# POWER_Management.net
KiCad netlist of a schematic drawn in Altium Designer
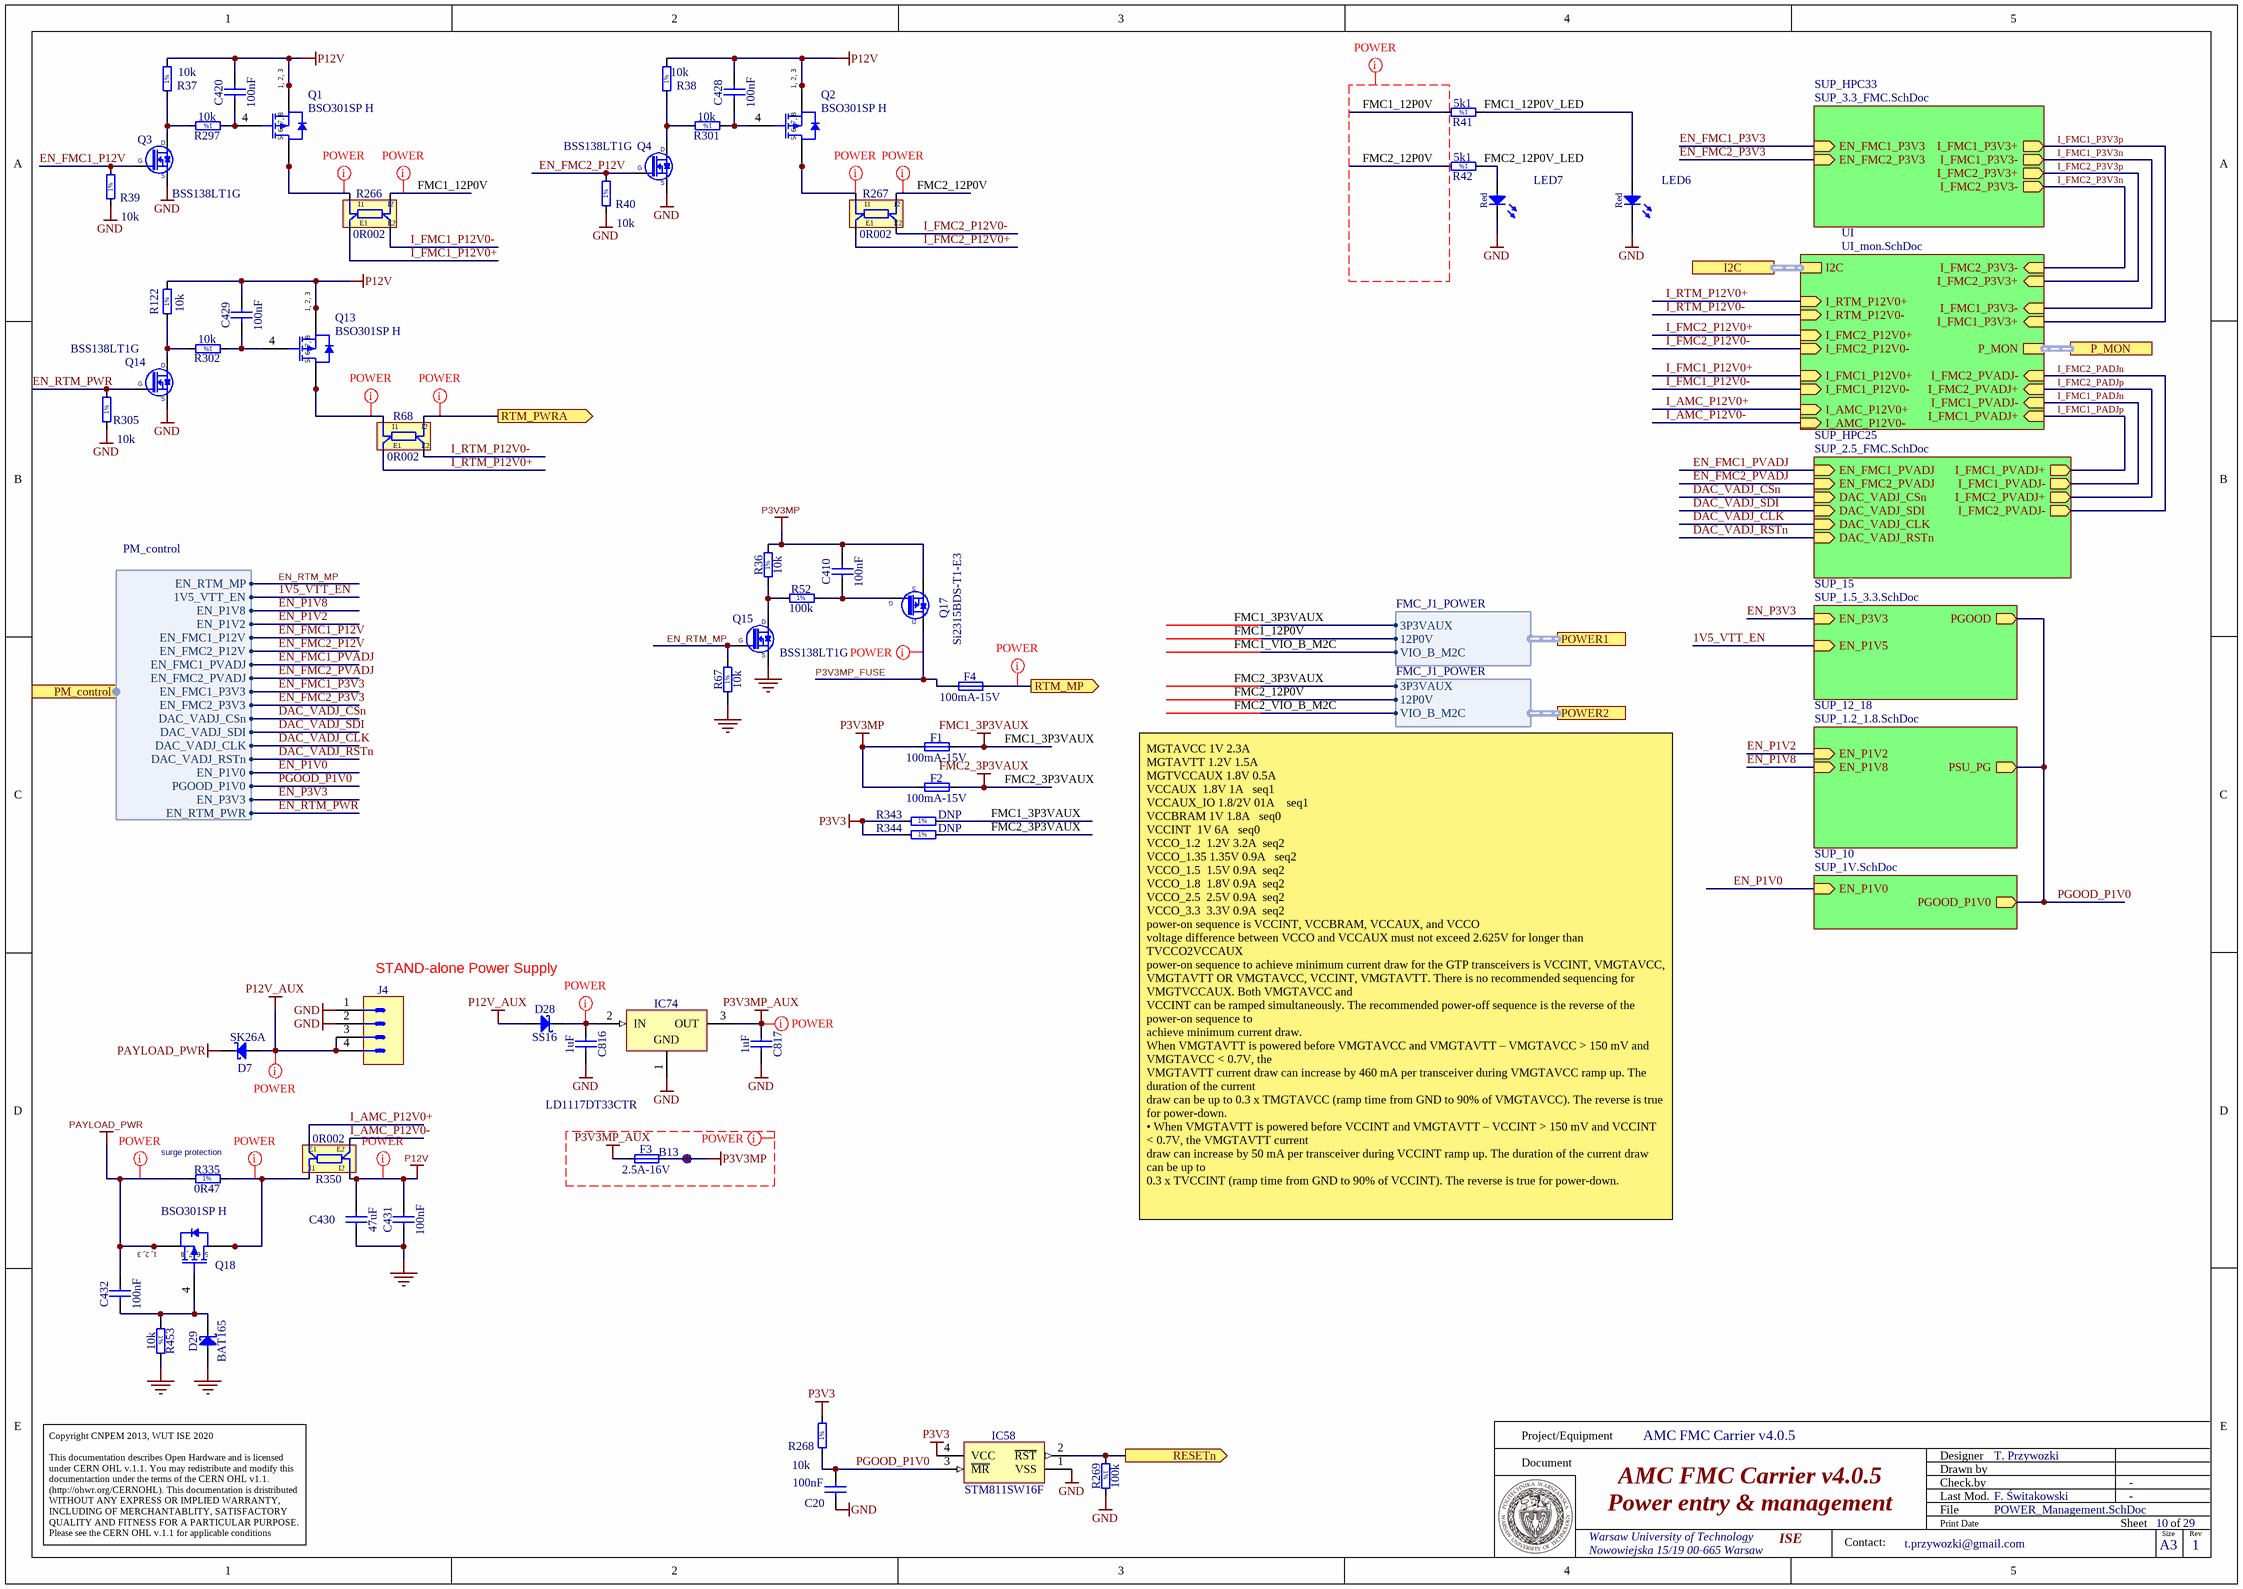
[diagram p0: POWER_Management.SchDoc]

(export (version "E")
  (design (tool "Eeschema 10.0.6"))
  (components
    (comp (ref "B13")
      (value "SMD Pad")
      (footprint "C100")
      (description "Through Hole Pad")
      (fields (field (name "PART NUMBER") "SMD_PAD_D1MM") (field (name "AUTHOR") "CERN DEM JLC"))
      (libsource (lib "Eletro-mechanical") (part "Single SMD Pad (Round)"))
    )
    (comp (ref "C20")
      (value "100nF")
      (footprint "CAPC0603X33N")
      (description "Non-polarised capacitor")
      (fields
        (field (name "PART NUMBER") "CC0201_100NF_6.3V_10%_X5R")
        (field (name "VOLTAGE") "6.3V")
        (field (name "AUTHOR") "CERN DEM JLC")
      )
      (libsource (lib "Capacitors") (part "Capacitor - non polarized"))
    )
    (comp (ref "C410")
      (value "100nF")
      (footprint "CAPC1005X55N")
      (description "Non-polarised capacitor")
      (fields
        (field (name "MANUFACTURER PART NUMBER") "CC0402_100NF_16V_10%_X5R")
        (field (name "MANUFACTURER") "GENERIC")
        (field (name "AUTHOR") "CERN DEM JLC")
      )
      (libsource (lib "Capacitors") (part "Capacitor - non polarized"))
    )
    (comp (ref "C420")
      (value "100nF")
      (footprint "CAPC1005X55N")
      (description "Non-polarised capacitor")
      (fields
        (field (name "MANUFACTURER PART NUMBER") "CC0402_100NF_16V_10%_X5R")
        (field (name "MANUFACTURER") "GENERIC")
        (field (name "AUTHOR") "CERN DEM JLC")
      )
      (libsource (lib "Capacitors") (part "Capacitor - non polarized"))
    )
    (comp (ref "C428")
      (value "100nF")
      (footprint "CAPC1005X55N")
      (description "Non-polarised capacitor")
      (fields
        (field (name "MANUFACTURER PART NUMBER") "CC0402_100NF_16V_10%_X5R")
        (field (name "MANUFACTURER") "GENERIC")
        (field (name "AUTHOR") "CERN DEM JLC")
      )
      (libsource (lib "Capacitors") (part "Capacitor - non polarized"))
    )
    (comp (ref "C429")
      (value "100nF")
      (footprint "CAPC1005X55N")
      (description "Non-polarised capacitor")
      (fields
        (field (name "MANUFACTURER PART NUMBER") "CC0402_100NF_16V_10%_X5R")
        (field (name "MANUFACTURER") "GENERIC")
        (field (name "AUTHOR") "CERN DEM JLC")
      )
      (libsource (lib "Capacitors") (part "Capacitor - non polarized"))
    )
    (comp (ref "C430")
      (value "47uF")
      (footprint "CAPC3216X180N")
      (description "Non-polarised capacitor")
      (fields
        (field (name "MANUFACTURER PART NUMBER") "CC1206_47UF_25V_20%_X5R")
        (field (name "MANUFACTURER") "GENERIC")
        (field (name "AUTHOR") "CERN DEM JLC")
      )
      (libsource (lib "Capacitors") (part "Capacitor - non polarized"))
    )
    (comp (ref "C431")
      (value "100nF")
      (footprint "CAPC1005X55N")
      (description "Non-polarised capacitor")
      (fields
        (field (name "MANUFACTURER PART NUMBER") "CC0402_100NF_16V_10%_X5R")
        (field (name "MANUFACTURER") "GENERIC")
        (field (name "AUTHOR") "CERN DEM JLC")
      )
      (libsource (lib "Capacitors") (part "Capacitor - non polarized"))
    )
    (comp (ref "C432")
      (value "100nF")
      (footprint "CAPC1005X55N")
      (description "Non-polarised capacitor")
      (fields
        (field (name "MANUFACTURER PART NUMBER") "CC0402_100NF_16V_10%_X5R")
        (field (name "MANUFACTURER") "GENERIC")
        (field (name "AUTHOR") "CERN DEM JLC")
      )
      (libsource (lib "Capacitors") (part "Capacitor - non polarized"))
    )
    (comp (ref "C816")
      (value "1uF")
      (footprint "CAPC1608X87N")
      (description "Non-polarised capacitor")
      (fields
        (field (name "PART NUMBER") "CC0603_1UF_16V_10%_X7R")
        (field (name "VOLTAGE") "16V")
        (field (name "AUTHOR") "CERN DEM JLC")
      )
      (libsource (lib "Capacitors") (part "Capacitor - non polarized"))
    )
    (comp (ref "C817")
      (value "1uF")
      (footprint "CAPC1608X87N")
      (description "Non-polarised capacitor")
      (fields
        (field (name "PART NUMBER") "CC0603_1UF_16V_10%_X7R")
        (field (name "VOLTAGE") "16V")
        (field (name "AUTHOR") "CERN DEM JLC")
      )
      (libsource (lib "Capacitors") (part "Capacitor - non polarized"))
    )
    (comp (ref "D7")
      (value "SK26A")
      (footprint "DIOM5126X265N")
      (description "Schottky Diode")
      (fields
        (field (name "VOLTAGE") "60V")
        (field (name "POWER") "2A")
        (field (name "AUTHOR") "CERN DEM JMW")
      )
      (libsource (lib "ICs And Semiconductors") (part "Diode Schottky"))
    )
    (comp (ref "D28")
      (value "SS16")
      (footprint "DIOM5127X229N")
      (description "Schottky Diode")
      (fields
        (field (name "MANUFACTURER") "VISHAY GENERAL SEMICONDUCTOR")
        (field (name "VOLTAGE") "60V")
        (field (name "AUTHOR") "CERN DEM JLC")
      )
      (libsource (lib "ICs And Semiconductors") (part "Diode Schottky"))
    )
    (comp (ref "D29")
      (value "BAT165")
      (footprint "SOD2512X110N")
      (description "Schottky Diode")
      (fields
        (field (name "MANUFACTURER") "INFINEON")
        (field (name "VOLTAGE") "40V")
        (field (name "AUTHOR") "CERN DEM JLC")
      )
      (libsource (lib "ICs And Semiconductors") (part "Diode Schottky"))
    )
    (comp (ref "F1")
      (value "100mA-15V")
      (footprint "FUSR_LITTELFUSE_0805L010")
      (description "Fuse")
      (fields
        (field (name "MANUFACTURER PART NUMBER") "0805L010YR")
        (field (name "MANUFACTURER") "LITTELFUSE")
        (field (name "AUTHOR") "CERN DEM JLC")
      )
      (libsource (lib "Eletro-mechanical") (part "Fuse"))
    )
    (comp (ref "F2")
      (value "100mA-15V")
      (footprint "FUSR_LITTELFUSE_0805L010")
      (description "Fuse")
      (fields
        (field (name "MANUFACTURER PART NUMBER") "0805L010YR")
        (field (name "MANUFACTURER") "LITTELFUSE")
        (field (name "AUTHOR") "CERN DEM JLC")
      )
      (libsource (lib "Eletro-mechanical") (part "Fuse"))
    )
    (comp (ref "F3")
      (value "2.5A-16V")
      (footprint "FUSR_BOURNS_MF-MSMF_STYLE2")
      (description "Fuse")
      (fields
        (field (name "PART NUMBER") "FUSR_BOURNS_MF-MSMF250/16X-2")
        (field (name "MANUFACTURER") "BOURNS")
        (field (name "AUTHOR") "CERN DEM JLC")
      )
      (libsource (lib "Eletro-mechanical") (part "Fuse"))
    )
    (comp (ref "F4")
      (value "100mA-15V")
      (footprint "FUSR_LITTELFUSE_0805L010")
      (description "Fuse")
      (fields
        (field (name "MANUFACTURER PART NUMBER") "0805L010YR")
        (field (name "MANUFACTURER") "LITTELFUSE")
        (field (name "AUTHOR") "CERN DEM JLC")
      )
      (libsource (lib "Eletro-mechanical") (part "Fuse"))
    )
    (comp (ref "IC58")
      (value "STM811SW16F")
      (footprint "SOT143N")
      (description "Microprocessor Reset Circuit")
      (fields (field (name "MANUFACTURER") "ST MICROELECTRONICS") (field (name "AUTHOR") "CERN DEM JLC"))
      (libsource (lib "ICs And Semiconductors") (part "STM811"))
    )
    (comp (ref "IC74")
      (value "LD1117DT33CTR")
      (footprint "TO228P972X240-3N-R540X510")
      (description "3-Terminal Regulator 1=GND 2=IN 3=OUT")
      (fields (field (name "MANUFACTURER") "ST MICROELECTRONICS") (field (name "AUTHOR") "CERN DEM JLC"))
      (libsource (lib "ICs And Semiconductors") (part "REG3 1GND-2IN-3OUT"))
    )
    (comp (ref "J4")
      (value "Mini-Fit Jr.™")
      (footprint "MOLEX_39-28-1043")
      (description "Connector 4 Male")
      (fields
        (field (name "PART NUMBER") "MOLEX_39-28-1043")
        (field (name "MANUFACTURER") "MOLEX")
        (field (name "AUTHOR") "CERN DEM JLC")
      )
      (libsource (lib "Connectors") (part "Connector 4 Male"))
    )
    (comp (ref "LED6")
      (value "Red")
      (footprint "LED_KINGBRIGHT_KPH-1608SURCK")
      (description "LED Red 1C 2A")
      (fields
        (field (name "PART NUMBER") "LED_KINGBRIGHT_KPH-1608SURCK")
        (field (name "MANUFACTURER") "KINGBRIGHT")
        (field (name "AUTHOR") "CERN DEM JLC")
      )
      (libsource (lib "ICs And Semiconductors") (part "LED Red 1C 2A"))
    )
    (comp (ref "LED7")
      (value "Red")
      (footprint "LED_KINGBRIGHT_KPH-1608SURCK")
      (description "LED Red 1C 2A")
      (fields
        (field (name "PART NUMBER") "LED_KINGBRIGHT_KPH-1608SURCK")
        (field (name "MANUFACTURER") "KINGBRIGHT")
        (field (name "AUTHOR") "CERN DEM JLC")
      )
      (libsource (lib "ICs And Semiconductors") (part "LED Red 1C 2A"))
    )
    (comp (ref "Q1")
      (value "BSO301SP H")
      (footprint "INF-P-DSO-8-3_L")
      (fields (field (name "MANUFACTURER") "Infineon"))
      (libsource (lib "Altium Content Vault") (part "INF-PEMOS-SSSGDDDD-8"))
    )
    (comp (ref "Q2")
      (value "BSO301SP H")
      (footprint "INF-P-DSO-8-3_L")
      (fields (field (name "MANUFACTURER") "Infineon"))
      (libsource (lib "Altium Content Vault") (part "INF-PEMOS-SSSGDDDD-8"))
    )
    (comp (ref "Q3")
      (value "BSS138LT1G")
      (footprint "SOT95P240X110-3N")
      (description "N-CHANNEL MOSFET WITH DIODE")
      (fields (field (name "MANUFACTURER") "ON SEMICONDUCTOR") (field (name "AUTHOR") "CERN DEM JLC"))
      (libsource (lib "ICs And Semiconductors") (part "N-MOSFET-D 1G 2S 3D"))
    )
    (comp (ref "Q4")
      (value "BSS138LT1G")
      (footprint "SOT95P240X110-3N")
      (description "N-CHANNEL MOSFET WITH DIODE")
      (fields (field (name "MANUFACTURER") "ON SEMICONDUCTOR") (field (name "AUTHOR") "CERN DEM JLC"))
      (libsource (lib "ICs And Semiconductors") (part "N-MOSFET-D 1G 2S 3D"))
    )
    (comp (ref "Q13")
      (value "BSO301SP H")
      (footprint "INF-P-DSO-8-3_L")
      (fields (field (name "MANUFACTURER") "Infineon"))
      (libsource (lib "Altium Content Vault") (part "INF-PEMOS-SSSGDDDD-8"))
    )
    (comp (ref "Q14")
      (value "BSS138LT1G")
      (footprint "SOT95P240X110-3N")
      (description "N-CHANNEL MOSFET WITH DIODE")
      (fields (field (name "MANUFACTURER") "ON SEMICONDUCTOR") (field (name "AUTHOR") "CERN DEM JLC"))
      (libsource (lib "ICs And Semiconductors") (part "N-MOSFET-D 1G 2S 3D"))
    )
    (comp (ref "Q15")
      (value "BSS138LT1G")
      (footprint "SOT95P240X110-3N")
      (description "N-CHANNEL MOSFET WITH DIODE")
      (fields (field (name "MANUFACTURER") "ON SEMICONDUCTOR") (field (name "AUTHOR") "CERN DEM JLC"))
      (libsource (lib "ICs And Semiconductors") (part "N-MOSFET-D 1G 2S 3D"))
    )
    (comp (ref "Q17")
      (value "Si2315BDS-T1-E3")
      (footprint "SOT95P237X112-3N")
      (description "P-CHANNEL MOSFET WITH DIODE")
      (fields (field (name "MANUFACTURER") "VISHAY SILICONIX") (field (name "AUTHOR") "CERN DEM JLC"))
      (libsource (lib "ICs And Semiconductors") (part "P-MOSFET-D 1G 2S 3D"))
    )
    (comp (ref "Q18")
      (value "BSO301SP H")
      (footprint "INF-P-DSO-8-3_L")
      (fields (field (name "MANUFACTURER") "Infineon"))
      (libsource (lib "Altium Content Vault") (part "INF-PEMOS-SSSGDDDD-8"))
    )
    (comp (ref "R36")
      (value "10k")
      (footprint "RESC1005X40N")
      (description "Resistor - 1%")
      (fields
        (field (name "MANUFACTURER PART NUMBER") "R0402_10K_1%_0.0625W_100PPM")
        (field (name "MANUFACTURER") "GENERIC")
        (field (name "AUTHOR") "CERN DEM JLC")
      )
      (libsource (lib "Resistors") (part "Resistor - 1%"))
    )
    (comp (ref "R37")
      (value "10k")
      (footprint "RESC1005X40N")
      (description "Resistor - 1%")
      (fields
        (field (name "PART NUMBER") "R0402_10K_1%_0.0625W_100PPM")
        (field (name "POWER") "0.0625W")
        (field (name "AUTHOR") "CERN DEM JLC")
      )
      (libsource (lib "Resistors") (part "Resistor - 1%"))
    )
    (comp (ref "R38")
      (value "10k")
      (footprint "RESC1005X40N")
      (description "Resistor - 1%")
      (fields
        (field (name "PART NUMBER") "R0402_10K_1%_0.0625W_100PPM")
        (field (name "POWER") "0.0625W")
        (field (name "AUTHOR") "CERN DEM JLC")
      )
      (libsource (lib "Resistors") (part "Resistor - 1%"))
    )
    (comp (ref "R39")
      (value "10k")
      (footprint "RESC1005X40N")
      (description "Resistor - 1%")
      (fields
        (field (name "PART NUMBER") "R0402_10K_1%_0.0625W_100PPM")
        (field (name "POWER") "0.0625W")
        (field (name "AUTHOR") "CERN DEM JLC")
      )
      (libsource (lib "Resistors") (part "Resistor - 1%"))
    )
    (comp (ref "R40")
      (value "10k")
      (footprint "RESC1005X40N")
      (description "Resistor - 1%")
      (fields
        (field (name "PART NUMBER") "R0402_10K_1%_0.0625W_100PPM")
        (field (name "POWER") "0.0625W")
        (field (name "AUTHOR") "CERN DEM JLC")
      )
      (libsource (lib "Resistors") (part "Resistor - 1%"))
    )
    (comp (ref "R41")
      (value "5k1")
      (footprint "RESC1608X55N")
      (description "Resistor - 1%")
      (fields
        (field (name "PART NUMBER") "R0603_5K1_1%_0.1W_100PPM")
        (field (name "POWER") "0.1W")
        (field (name "AUTHOR") "CERN DEM JLC")
      )
      (libsource (lib "Resistors") (part "Resistor - 1%"))
    )
    (comp (ref "R42")
      (value "5k1")
      (footprint "RESC1608X55N")
      (description "Resistor - 1%")
      (fields
        (field (name "PART NUMBER") "R0603_5K1_1%_0.1W_100PPM")
        (field (name "POWER") "0.1W")
        (field (name "AUTHOR") "CERN DEM JLC")
      )
      (libsource (lib "Resistors") (part "Resistor - 1%"))
    )
    (comp (ref "R52")
      (value "100k")
      (footprint "RESC1005X40N")
      (description "Resistor - 1%")
      (fields
        (field (name "MANUFACTURER PART NUMBER") "R0402_100K_1%_0.0625W_100PPM")
        (field (name "MANUFACTURER") "GENERIC")
        (field (name "AUTHOR") "CERN DEM JLC")
      )
      (libsource (lib "Resistors") (part "Resistor - 1%"))
    )
    (comp (ref "R67")
      (value "10k")
      (footprint "RESC1005X40N")
      (description "Resistor - 1%")
      (fields
        (field (name "MANUFACTURER PART NUMBER") "R0402_10K_1%_0.0625W_100PPM")
        (field (name "MANUFACTURER") "GENERIC")
        (field (name "AUTHOR") "CERN DEM JLC")
      )
      (libsource (lib "Resistors") (part "Resistor - 1%"))
    )
    (comp (ref "R68")
      (value "0R002")
      (footprint "RES_VISHAY_WSK2512_0R005-0R2")
      (description "Power and Current Sensing Resistor")
      (fields
        (field (name "PART NUMBER") "R2512_0R002_1%_1W_35PPM_VISHAY_WSK")
        (field (name "POWER") "1W")
        (field (name "AUTHOR") "CERN DEM MR")
      )
      (libsource (lib "Resistors") (part "Current Sense Resistor"))
    )
    (comp (ref "R122")
      (value "10k")
      (footprint "RESC1005X40N")
      (description "Resistor - 1%")
      (fields
        (field (name "PART NUMBER") "R0402_10K_1%_0.0625W_100PPM")
        (field (name "POWER") "0.0625W")
        (field (name "AUTHOR") "CERN DEM JLC")
      )
      (libsource (lib "Resistors") (part "Resistor - 1%"))
    )
    (comp (ref "R266")
      (value "0R002")
      (footprint "RES_VISHAY_WSK2512_0R005-0R2")
      (description "Power and Current Sensing Resistor")
      (fields
        (field (name "PART NUMBER") "R2512_0R002_1%_1W_35PPM_VISHAY_WSK")
        (field (name "POWER") "1W")
        (field (name "AUTHOR") "CERN DEM MR")
      )
      (libsource (lib "Resistors") (part "Current Sense Resistor"))
    )
    (comp (ref "R267")
      (value "0R002")
      (footprint "RES_VISHAY_WSK2512_0R005-0R2")
      (description "Power and Current Sensing Resistor")
      (fields
        (field (name "PART NUMBER") "R2512_0R002_1%_1W_35PPM_VISHAY_WSK")
        (field (name "POWER") "1W")
        (field (name "AUTHOR") "CERN DEM MR")
      )
      (libsource (lib "Resistors") (part "Current Sense Resistor"))
    )
    (comp (ref "R268")
      (value "10k")
      (footprint "RESC1005X40N")
      (description "Resistor - 1%")
      (fields
        (field (name "PART NUMBER") "R0402_10K_1%_0.0625W_100PPM")
        (field (name "POWER") "0.0625W")
        (field (name "AUTHOR") "CERN DEM JLC")
      )
      (libsource (lib "Resistors") (part "Resistor - 1%"))
    )
    (comp (ref "R269")
      (value "100k")
      (footprint "RESC1005X40N")
      (description "Resistor - 1%")
      (fields
        (field (name "PART NUMBER") "R0402_100K_1%_0.0625W_100PPM")
        (field (name "POWER") "0.0625W")
        (field (name "AUTHOR") "CERN DEM JLC")
      )
      (libsource (lib "Resistors") (part "Resistor - 1%"))
    )
    (comp (ref "R297")
      (value "10k")
      (footprint "RESC1005X40N")
      (description "Resistor - 1%")
      (fields
        (field (name "MANUFACTURER PART NUMBER") "R0402_10K_1%_0.0625W_100PPM")
        (field (name "MANUFACTURER") "GENERIC")
        (field (name "AUTHOR") "CERN DEM JLC")
      )
      (libsource (lib "Resistors") (part "Resistor - 1%"))
    )
    (comp (ref "R301")
      (value "10k")
      (footprint "RESC1005X40N")
      (description "Resistor - 1%")
      (fields
        (field (name "MANUFACTURER PART NUMBER") "R0402_10K_1%_0.0625W_100PPM")
        (field (name "MANUFACTURER") "GENERIC")
        (field (name "AUTHOR") "CERN DEM JLC")
      )
      (libsource (lib "Resistors") (part "Resistor - 1%"))
    )
    (comp (ref "R302")
      (value "10k")
      (footprint "RESC1005X40N")
      (description "Resistor - 1%")
      (fields
        (field (name "MANUFACTURER PART NUMBER") "R0402_10K_1%_0.0625W_100PPM")
        (field (name "MANUFACTURER") "GENERIC")
        (field (name "AUTHOR") "CERN DEM JLC")
      )
      (libsource (lib "Resistors") (part "Resistor - 1%"))
    )
    (comp (ref "R305")
      (value "10k")
      (footprint "RESC1005X40N")
      (description "Resistor - 1%")
      (fields
        (field (name "PART NUMBER") "R0402_10K_1%_0.0625W_100PPM")
        (field (name "POWER") "0.0625W")
        (field (name "AUTHOR") "CERN DEM JLC")
      )
      (libsource (lib "Resistors") (part "Resistor - 1%"))
    )
    (comp (ref "R335")
      (value "0R47")
      (footprint "RESC3216X65N")
      (description "Resistor - 1%")
      (fields
        (field (name "MANUFACTURER PART NUMBER") "RL1206FR-7W0R47  (35051914707)")
        (field (name "MANUFACTURER") "YAGEO PHYCOMP")
        (field (name "AUTHOR") "CERN DEM JLC")
      )
      (libsource (lib "Resistors") (part "Resistor - 1%"))
    )
    (comp (ref "R343")
      (value "DNP")
      (footprint "RESC1005X40N")
      (description "Resistor - 1%")
      (fields
        (field (name "PART NUMBER") "R0402_0R_JUMPER")
        (field (name "MANUFACTURER") "GENERIC")
        (field (name "AUTHOR") "CERN DEM JLC")
      )
      (libsource (lib "Resistors") (part "Resistor - 1%"))
    )
    (comp (ref "R344")
      (value "DNP")
      (footprint "RESC1005X40N")
      (description "Resistor - 1%")
      (fields
        (field (name "PART NUMBER") "R0402_0R_JUMPER")
        (field (name "MANUFACTURER") "GENERIC")
        (field (name "AUTHOR") "CERN DEM JLC")
      )
      (libsource (lib "Resistors") (part "Resistor - 1%"))
    )
    (comp (ref "R350")
      (value "0R002")
      (footprint "RES_VISHAY_WSK2512_0R005-0R2")
      (description "Power and Current Sensing Resistor")
      (fields
        (field (name "PART NUMBER") "R2512_0R002_1%_1W_35PPM_VISHAY_WSK")
        (field (name "POWER") "1W")
        (field (name "AUTHOR") "CERN DEM MR")
      )
      (libsource (lib "") (part "Current Sense Resistor_1"))
    )
    (comp (ref "R453")
      (value "10k")
      (footprint "RESC1005X40N")
      (description "Resistor - 1%")
      (fields
        (field (name "MANUFACTURER PART NUMBER") "R0402_10K_1%_0.0625W_100PPM")
        (field (name "MANUFACTURER") "GENERIC")
        (field (name "AUTHOR") "CERN DEM JLC")
      )
      (libsource (lib "Resistors") (part "Resistor - 1%"))
    )
  )
  (nets
    (net (code "11") (name "/EN_FMC1_P12V") (class "Default")
      (node (ref "Q3") (pin "1") (pinfunction "G_1") (pintype "passive"))
      (node (ref "R39") (pin "2") (pinfunction "2_2") (pintype "passive"))
    )
    (net (code "14") (name "/EN_FMC2_P12V") (class "Default")
      (node (ref "Q4") (pin "1") (pinfunction "G_1") (pintype "passive"))
      (node (ref "R40") (pin "2") (pinfunction "2_2") (pintype "passive"))
    )
    (net (code "20") (name "/EN_RTM_MP") (class "Default")
      (node (ref "Q15") (pin "1") (pinfunction "G_1") (pintype "passive"))
      (node (ref "R67") (pin "2") (pinfunction "2_2") (pintype "passive"))
    )
    (net (code "21") (name "/EN_RTM_PWR") (class "Default")
      (node (ref "Q14") (pin "1") (pinfunction "G_1") (pintype "passive"))
      (node (ref "R305") (pin "2") (pinfunction "2_2") (pintype "passive"))
    )
    (net (code "22") (name "/FMC1_12P0V") (class "Default")
      (node (ref "R266") (pin "I2") (pinfunction "I2_I2") (pintype "passive"))
      (node (ref "R41") (pin "2") (pinfunction "2_2") (pintype "passive"))
    )
    (net (code "23") (name "/FMC1_12P0V_LED") (class "Default")
      (node (ref "LED6") (pin "2") (pinfunction "A_2") (pintype "passive"))
      (node (ref "R41") (pin "1") (pinfunction "1_1") (pintype "passive"))
    )
    (net (code "25") (name "/FMC2_12P0V") (class "Default")
      (node (ref "R267") (pin "I2") (pinfunction "I2_I2") (pintype "passive"))
      (node (ref "R42") (pin "2") (pinfunction "2_2") (pintype "passive"))
    )
    (net (code "26") (name "/FMC2_12P0V_LED") (class "Default")
      (node (ref "LED7") (pin "2") (pinfunction "A_2") (pintype "passive"))
      (node (ref "R42") (pin "1") (pinfunction "1_1") (pintype "passive"))
    )
    (net (code "29") (name "/I_AMC_P12V0+") (class "Default")
      (node (ref "R350") (pin "E1") (pinfunction "E1_E1") (pintype "passive"))
    )
    (net (code "30") (name "/I_AMC_P12V0-") (class "Default")
      (node (ref "R350") (pin "E2") (pinfunction "E2_E2") (pintype "passive"))
    )
    (net (code "33") (name "/I_FMC1_P12V0+") (class "Default")
      (node (ref "R266") (pin "E1") (pinfunction "E1_E1") (pintype "passive"))
    )
    (net (code "34") (name "/I_FMC1_P12V0-") (class "Default")
      (node (ref "R266") (pin "E2") (pinfunction "E2_E2") (pintype "passive"))
    )
    (net (code "39") (name "/I_FMC2_P12V0+") (class "Default")
      (node (ref "R267") (pin "E1") (pinfunction "E1_E1") (pintype "passive"))
    )
    (net (code "40") (name "/I_FMC2_P12V0-") (class "Default")
      (node (ref "R267") (pin "E2") (pinfunction "E2_E2") (pintype "passive"))
    )
    (net (code "43") (name "/I_RTM_P12V0+") (class "Default")
      (node (ref "R68") (pin "E1") (pinfunction "E1_E1") (pintype "passive"))
    )
    (net (code "44") (name "/I_RTM_P12V0-") (class "Default")
      (node (ref "R68") (pin "E2") (pinfunction "E2_E2") (pintype "passive"))
    )
    (net (code "45") (name "/P3V3MP_FUSE") (class "Default")
      (node (ref "F4") (pin "1") (pinfunction "1_1") (pintype "passive"))
      (node (ref "Q17") (pin "3") (pinfunction "D_3") (pintype "passive"))
    )
    (net (code "46") (name "/PGOOD_P1V0") (class "Default")
      (node (ref "C20") (pin "1") (pinfunction "1_1") (pintype "passive"))
      (node (ref "IC58") (pin "3") (pinfunction "~{MR}_3") (pintype "input"))
      (node (ref "R268") (pin "1") (pinfunction "1_1") (pintype "passive"))
    )
    (net (code "48") (name "/RESETn") (class "Default")
      (node (ref "IC58") (pin "2") (pinfunction "~{RST}_2") (pintype "output"))
      (node (ref "R269") (pin "1") (pinfunction "1_1") (pintype "passive"))
    )
    (net (code "49") (name "/RTM_MP") (class "Default")
      (node (ref "F4") (pin "2") (pinfunction "2_2") (pintype "passive"))
    )
    (net (code "50") (name "/RTM_PWRA") (class "Default")
      (node (ref "R68") (pin "I2") (pinfunction "I2_I2") (pintype "passive"))
    )
    (net (code "53") (name "FMC1_3P3VAUX") (class "Default")
      (node (ref "F1") (pin "2") (pinfunction "2_2") (pintype "passive"))
      (node (ref "R343") (pin "2") (pinfunction "2_2") (pintype "passive"))
    )
    (net (code "54") (name "FMC2_3P3VAUX") (class "Default")
      (node (ref "F2") (pin "2") (pinfunction "2_2") (pintype "passive"))
      (node (ref "R344") (pin "2") (pinfunction "2_2") (pintype "passive"))
    )
    (net (code "55") (name "GND") (class "Default")
      (node (ref "C20") (pin "2") (pinfunction "2_2") (pintype "passive"))
      (node (ref "C430") (pin "1") (pinfunction "1_1") (pintype "passive"))
      (node (ref "C431") (pin "1") (pinfunction "1_1") (pintype "passive"))
      (node (ref "C816") (pin "2") (pinfunction "2_2") (pintype "passive"))
      (node (ref "C817") (pin "2") (pinfunction "2_2") (pintype "passive"))
      (node (ref "D29") (pin "2") (pinfunction "A_2") (pintype "passive"))
      (node (ref "IC58") (pin "1") (pinfunction "VSS_1") (pintype "power_in"))
      (node (ref "IC74") (pin "1") (pinfunction "GND_1") (pintype "power_in"))
      (node (ref "J4") (pin "1") (pinfunction "1_1") (pintype "passive"))
      (node (ref "J4") (pin "2") (pinfunction "2_2") (pintype "passive"))
      (node (ref "LED6") (pin "1") (pinfunction "C_1") (pintype "passive"))
      (node (ref "LED7") (pin "1") (pinfunction "C_1") (pintype "passive"))
      (node (ref "Q14") (pin "2") (pinfunction "S_2") (pintype "passive"))
      (node (ref "Q15") (pin "2") (pinfunction "S_2") (pintype "passive"))
      (node (ref "Q3") (pin "2") (pinfunction "S_2") (pintype "passive"))
      (node (ref "Q4") (pin "2") (pinfunction "S_2") (pintype "passive"))
      (node (ref "R269") (pin "2") (pinfunction "2_2") (pintype "passive"))
      (node (ref "R305") (pin "1") (pinfunction "1_1") (pintype "passive"))
      (node (ref "R39") (pin "1") (pinfunction "1_1") (pintype "passive"))
      (node (ref "R40") (pin "1") (pinfunction "1_1") (pintype "passive"))
      (node (ref "R453") (pin "2") (pinfunction "2_2") (pintype "passive"))
      (node (ref "R67") (pin "1") (pinfunction "1_1") (pintype "passive"))
    )
    (net (code "56") (name "Net-(D28-C)") (class "Default")
      (node (ref "C816") (pin "1") (pinfunction "1_1") (pintype "passive"))
      (node (ref "D28") (pin "1") (pinfunction "C_1") (pintype "passive"))
      (node (ref "IC74") (pin "2") (pinfunction "IN_2") (pintype "input"))
    )
    (net (code "57") (name "Net-(D29-C)") (class "Default")
      (node (ref "C432") (pin "1") (pinfunction "1_1") (pintype "passive"))
      (node (ref "D29") (pin "1") (pinfunction "C_1") (pintype "passive"))
      (node (ref "Q18") (pin "4") (pinfunction "GATE_4") (pintype "passive"))
      (node (ref "R453") (pin "1") (pinfunction "1_1") (pintype "passive"))
    )
    (net (code "58") (name "Net-(Q1-DRAIN-Pad5)") (class "Default")
      (node (ref "Q1") (pin "5") (pinfunction "DRAIN_5") (pintype "passive"))
      (node (ref "Q1") (pin "6") (pinfunction "DRAIN_6") (pintype "passive"))
      (node (ref "Q1") (pin "7") (pinfunction "DRAIN_7") (pintype "passive"))
      (node (ref "Q1") (pin "8") (pinfunction "DRAIN_8") (pintype "passive"))
      (node (ref "R266") (pin "I1") (pinfunction "I1_I1") (pintype "passive"))
    )
    (net (code "59") (name "Net-(Q1-GATE)") (class "Default")
      (node (ref "C420") (pin "1") (pinfunction "1_1") (pintype "passive"))
      (node (ref "Q1") (pin "4") (pinfunction "GATE_4") (pintype "passive"))
      (node (ref "R297") (pin "1") (pinfunction "1_1") (pintype "passive"))
    )
    (net (code "60") (name "Net-(Q2-DRAIN-Pad5)") (class "Default")
      (node (ref "Q2") (pin "5") (pinfunction "DRAIN_5") (pintype "passive"))
      (node (ref "Q2") (pin "6") (pinfunction "DRAIN_6") (pintype "passive"))
      (node (ref "Q2") (pin "7") (pinfunction "DRAIN_7") (pintype "passive"))
      (node (ref "Q2") (pin "8") (pinfunction "DRAIN_8") (pintype "passive"))
      (node (ref "R267") (pin "I1") (pinfunction "I1_I1") (pintype "passive"))
    )
    (net (code "61") (name "Net-(Q2-GATE)") (class "Default")
      (node (ref "C428") (pin "1") (pinfunction "1_1") (pintype "passive"))
      (node (ref "Q2") (pin "4") (pinfunction "GATE_4") (pintype "passive"))
      (node (ref "R301") (pin "1") (pinfunction "1_1") (pintype "passive"))
    )
    (net (code "62") (name "Net-(Q3-D)") (class "Default")
      (node (ref "Q3") (pin "3") (pinfunction "D_3") (pintype "passive"))
      (node (ref "R297") (pin "2") (pinfunction "2_2") (pintype "passive"))
      (node (ref "R37") (pin "1") (pinfunction "1_1") (pintype "passive"))
    )
    (net (code "63") (name "Net-(Q4-D)") (class "Default")
      (node (ref "Q4") (pin "3") (pinfunction "D_3") (pintype "passive"))
      (node (ref "R301") (pin "2") (pinfunction "2_2") (pintype "passive"))
      (node (ref "R38") (pin "1") (pinfunction "1_1") (pintype "passive"))
    )
    (net (code "64") (name "Net-(Q13-DRAIN-Pad5)") (class "Default")
      (node (ref "Q13") (pin "5") (pinfunction "DRAIN_5") (pintype "passive"))
      (node (ref "Q13") (pin "6") (pinfunction "DRAIN_6") (pintype "passive"))
      (node (ref "Q13") (pin "7") (pinfunction "DRAIN_7") (pintype "passive"))
      (node (ref "Q13") (pin "8") (pinfunction "DRAIN_8") (pintype "passive"))
      (node (ref "R68") (pin "I1") (pinfunction "I1_I1") (pintype "passive"))
    )
    (net (code "65") (name "Net-(Q13-GATE)") (class "Default")
      (node (ref "C429") (pin "1") (pinfunction "1_1") (pintype "passive"))
      (node (ref "Q13") (pin "4") (pinfunction "GATE_4") (pintype "passive"))
      (node (ref "R302") (pin "1") (pinfunction "1_1") (pintype "passive"))
    )
    (net (code "66") (name "Net-(Q14-D)") (class "Default")
      (node (ref "Q14") (pin "3") (pinfunction "D_3") (pintype "passive"))
      (node (ref "R122") (pin "1") (pinfunction "1_1") (pintype "passive"))
      (node (ref "R302") (pin "2") (pinfunction "2_2") (pintype "passive"))
    )
    (net (code "67") (name "Net-(Q15-D)") (class "Default")
      (node (ref "Q15") (pin "3") (pinfunction "D_3") (pintype "passive"))
      (node (ref "R36") (pin "1") (pinfunction "1_1") (pintype "passive"))
      (node (ref "R52") (pin "2") (pinfunction "2_2") (pintype "passive"))
    )
    (net (code "68") (name "Net-(Q17-G)") (class "Default")
      (node (ref "C410") (pin "1") (pinfunction "1_1") (pintype "passive"))
      (node (ref "Q17") (pin "1") (pinfunction "G_1") (pintype "passive"))
      (node (ref "R52") (pin "1") (pinfunction "1_1") (pintype "passive"))
    )
    (net (code "69") (name "Net-(Q18-DRAIN-Pad5)") (class "Default")
      (node (ref "Q18") (pin "5") (pinfunction "DRAIN_5") (pintype "passive"))
      (node (ref "Q18") (pin "6") (pinfunction "DRAIN_6") (pintype "passive"))
      (node (ref "Q18") (pin "7") (pinfunction "DRAIN_7") (pintype "passive"))
      (node (ref "Q18") (pin "8") (pinfunction "DRAIN_8") (pintype "passive"))
      (node (ref "R335") (pin "2") (pinfunction "2_2") (pintype "passive"))
      (node (ref "R350") (pin "I1") (pinfunction "I1_I1") (pintype "passive"))
    )
    (net (code "70") (name "P3V3") (class "Default")
      (node (ref "IC58") (pin "4") (pinfunction "VCC_4") (pintype "power_in"))
      (node (ref "R268") (pin "2") (pinfunction "2_2") (pintype "passive"))
      (node (ref "R343") (pin "1") (pinfunction "1_1") (pintype "passive"))
      (node (ref "R344") (pin "1") (pinfunction "1_1") (pintype "passive"))
    )
    (net (code "71") (name "P3V3MP") (class "Default")
      (node (ref "B13") (pin "1") (pinfunction "1_1") (pintype "bidirectional"))
      (node (ref "C410") (pin "2") (pinfunction "2_2") (pintype "passive"))
      (node (ref "F1") (pin "1") (pinfunction "1_1") (pintype "passive"))
      (node (ref "F2") (pin "1") (pinfunction "1_1") (pintype "passive"))
      (node (ref "F3") (pin "1") (pinfunction "1_1") (pintype "passive"))
      (node (ref "Q17") (pin "2") (pinfunction "S_2") (pintype "passive"))
      (node (ref "R36") (pin "2") (pinfunction "2_2") (pintype "passive"))
    )
    (net (code "72") (name "P3V3MP_AUX") (class "Default")
      (node (ref "C817") (pin "1") (pinfunction "1_1") (pintype "passive"))
      (node (ref "F3") (pin "2") (pinfunction "2_2") (pintype "passive"))
      (node (ref "IC74") (pin "3") (pinfunction "OUT_3") (pintype "power_in"))
    )
    (net (code "73") (name "P12V") (class "Default")
      (node (ref "C420") (pin "2") (pinfunction "2_2") (pintype "passive"))
      (node (ref "C428") (pin "2") (pinfunction "2_2") (pintype "passive"))
      (node (ref "C429") (pin "2") (pinfunction "2_2") (pintype "passive"))
      (node (ref "C430") (pin "2") (pinfunction "2_2") (pintype "passive"))
      (node (ref "C431") (pin "2") (pinfunction "2_2") (pintype "passive"))
      (node (ref "Q1") (pin "1") (pinfunction "SOURCE_1") (pintype "passive"))
      (node (ref "Q1") (pin "2") (pinfunction "SOURCE_2") (pintype "passive"))
      (node (ref "Q1") (pin "3") (pinfunction "SOURCE_3") (pintype "passive"))
      (node (ref "Q13") (pin "1") (pinfunction "SOURCE_1") (pintype "passive"))
      (node (ref "Q13") (pin "2") (pinfunction "SOURCE_2") (pintype "passive"))
      (node (ref "Q13") (pin "3") (pinfunction "SOURCE_3") (pintype "passive"))
      (node (ref "Q2") (pin "1") (pinfunction "SOURCE_1") (pintype "passive"))
      (node (ref "Q2") (pin "2") (pinfunction "SOURCE_2") (pintype "passive"))
      (node (ref "Q2") (pin "3") (pinfunction "SOURCE_3") (pintype "passive"))
      (node (ref "R122") (pin "2") (pinfunction "2_2") (pintype "passive"))
      (node (ref "R350") (pin "I2") (pinfunction "I2_I2") (pintype "passive"))
      (node (ref "R37") (pin "2") (pinfunction "2_2") (pintype "passive"))
      (node (ref "R38") (pin "2") (pinfunction "2_2") (pintype "passive"))
    )
    (net (code "74") (name "P12V_AUX") (class "Default")
      (node (ref "D28") (pin "2") (pinfunction "A_2") (pintype "passive"))
      (node (ref "D7") (pin "2") (pinfunction "A_2") (pintype "passive"))
      (node (ref "J4") (pin "3") (pinfunction "3_3") (pintype "passive"))
      (node (ref "J4") (pin "4") (pinfunction "4_4") (pintype "passive"))
    )
    (net (code "75") (name "PAYLOAD_PWR") (class "Default")
      (node (ref "C432") (pin "2") (pinfunction "2_2") (pintype "passive"))
      (node (ref "D7") (pin "1") (pinfunction "C_1") (pintype "passive"))
      (node (ref "Q18") (pin "1") (pinfunction "SOURCE_1") (pintype "passive"))
      (node (ref "Q18") (pin "2") (pinfunction "SOURCE_2") (pintype "passive"))
      (node (ref "Q18") (pin "3") (pinfunction "SOURCE_3") (pintype "passive"))
      (node (ref "R335") (pin "1") (pinfunction "1_1") (pintype "passive"))
    )
  )
)
